# draft2.net
KiCad netlist of a schematic drawn in EAGLE
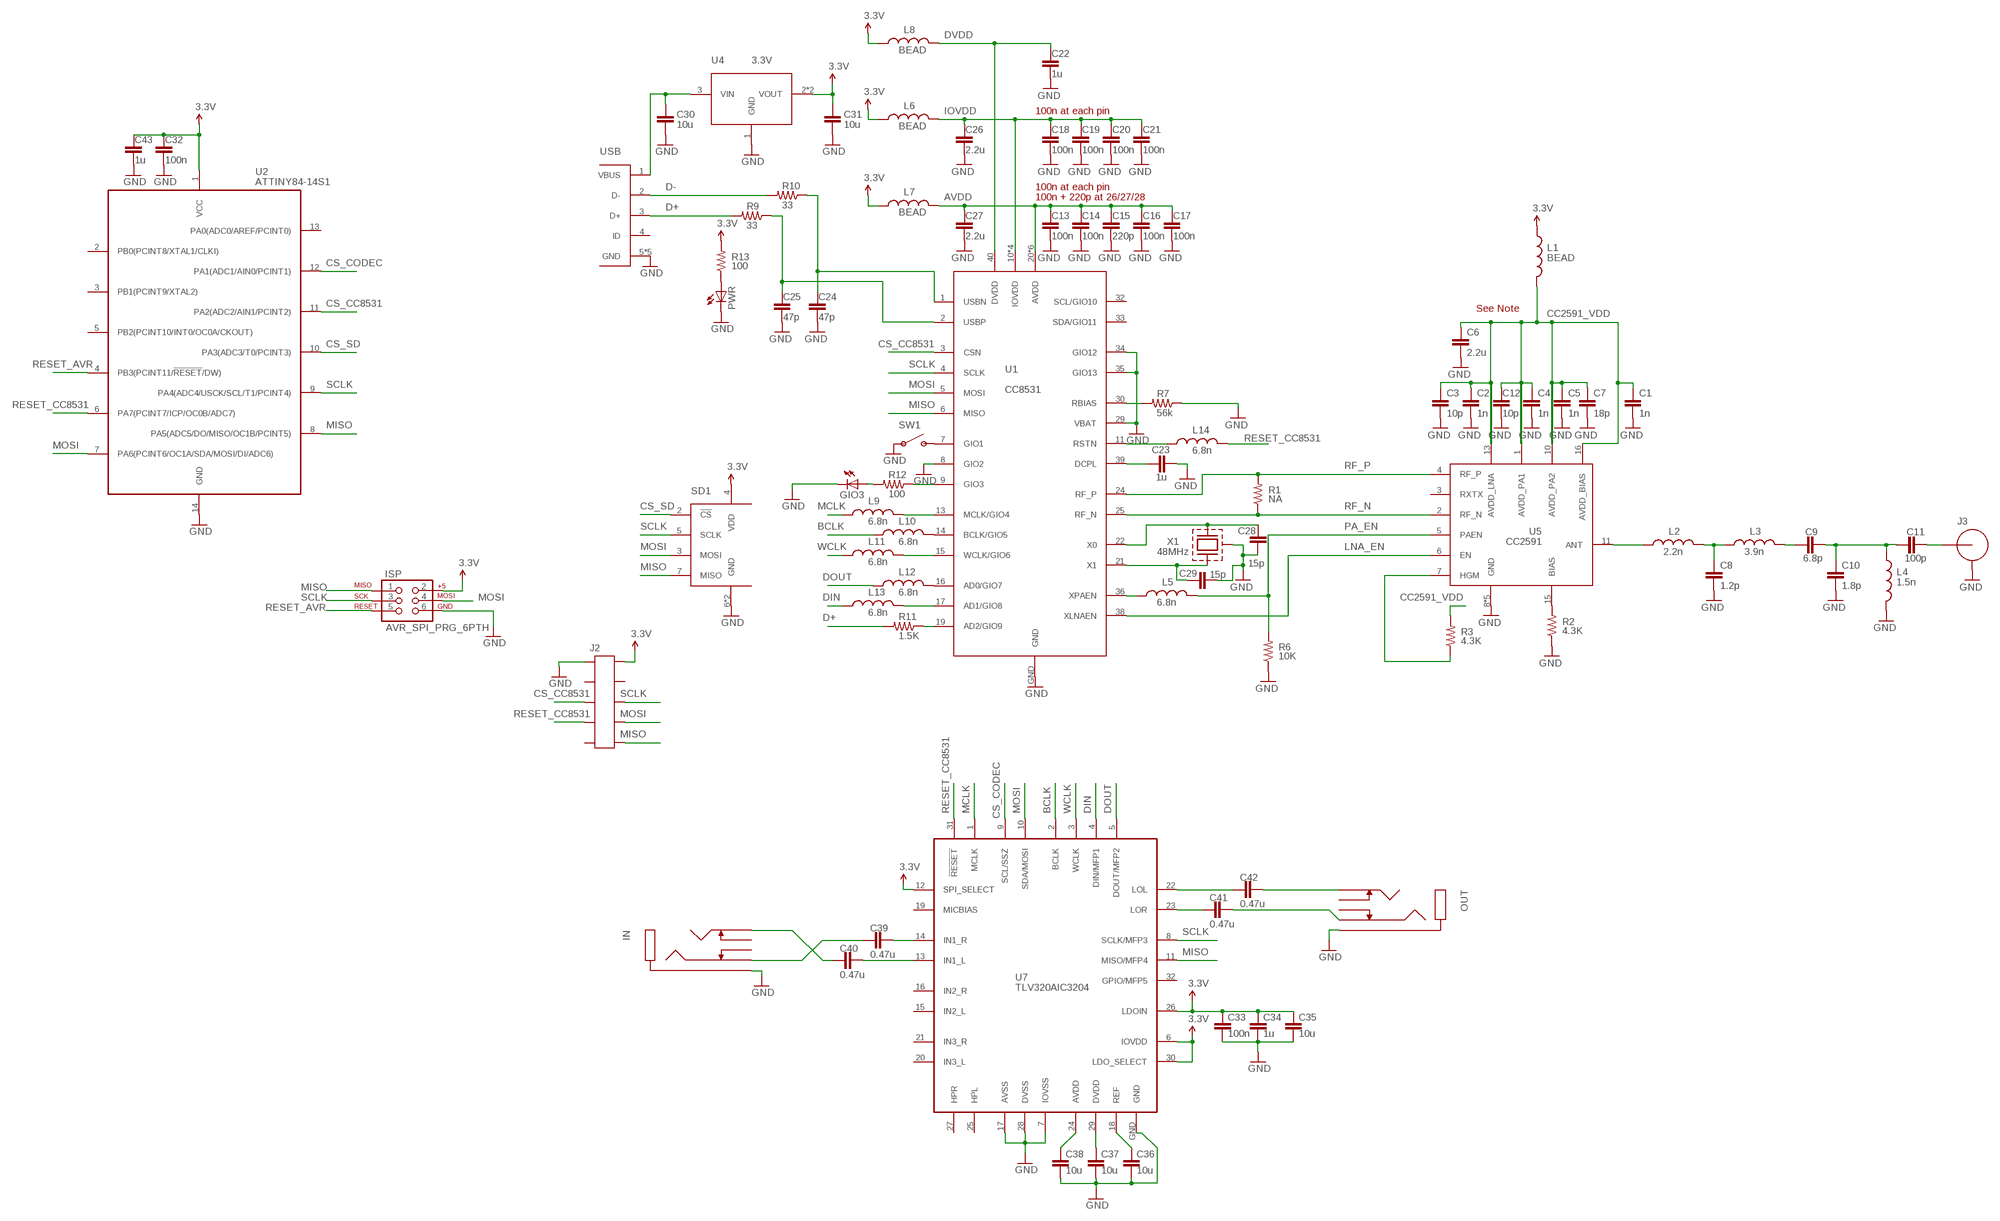
[diagram p0: schematic, sheet 1]

(export (version "E")
  (design (tool "Eeschema 10.0.6"))
  (components
    (comp (ref "C1")
      (value "1n")
      (footprint "eagle-import:C0603")
      (libsource (lib "eagle-import") (part "C-EUC0603"))
    )
    (comp (ref "C2")
      (value "1n")
      (footprint "eagle-import:C0603")
      (libsource (lib "eagle-import") (part "C-EUC0603"))
    )
    (comp (ref "C3")
      (value "10p")
      (footprint "eagle-import:C0603")
      (libsource (lib "eagle-import") (part "C-EUC0603"))
    )
    (comp (ref "C4")
      (value "1n")
      (footprint "eagle-import:C0603")
      (libsource (lib "eagle-import") (part "C-EUC0603"))
    )
    (comp (ref "C5")
      (value "1n")
      (footprint "eagle-import:C0603")
      (libsource (lib "eagle-import") (part "C-EUC0603"))
    )
    (comp (ref "C6")
      (value "2.2u")
      (footprint "eagle-import:C0603")
      (libsource (lib "eagle-import") (part "C-EUC0603"))
    )
    (comp (ref "C7")
      (value "18p")
      (footprint "eagle-import:C0603")
      (libsource (lib "eagle-import") (part "C-EUC0603"))
    )
    (comp (ref "C8")
      (value "1.2p")
      (footprint "eagle-import:C0603")
      (libsource (lib "eagle-import") (part "C-EUC0603"))
    )
    (comp (ref "C9")
      (value "6.8p")
      (footprint "eagle-import:C0603")
      (libsource (lib "eagle-import") (part "C-EUC0603"))
    )
    (comp (ref "C10")
      (value "1.8p")
      (footprint "eagle-import:C0603")
      (libsource (lib "eagle-import") (part "C-EUC0603"))
    )
    (comp (ref "C11")
      (value "100p")
      (footprint "eagle-import:C0603")
      (libsource (lib "eagle-import") (part "C-EUC0603"))
    )
    (comp (ref "C12")
      (value "10p")
      (footprint "eagle-import:C0603")
      (libsource (lib "eagle-import") (part "C-EUC0603"))
    )
    (comp (ref "C13")
      (value "100n")
      (footprint "eagle-import:C0603")
      (libsource (lib "eagle-import") (part "C-EUC0603"))
    )
    (comp (ref "C14")
      (value "100n")
      (footprint "eagle-import:C0603")
      (libsource (lib "eagle-import") (part "C-EUC0603"))
    )
    (comp (ref "C15")
      (value "220p")
      (footprint "eagle-import:C0603")
      (libsource (lib "eagle-import") (part "C-EUC0603"))
    )
    (comp (ref "C16")
      (value "100n")
      (footprint "eagle-import:C0603")
      (libsource (lib "eagle-import") (part "C-EUC0603"))
    )
    (comp (ref "C17")
      (value "100n")
      (footprint "eagle-import:C0603")
      (libsource (lib "eagle-import") (part "C-EUC0603"))
    )
    (comp (ref "C18")
      (value "100n")
      (footprint "eagle-import:C0603")
      (libsource (lib "eagle-import") (part "C-EUC0603"))
    )
    (comp (ref "C19")
      (value "100n")
      (footprint "eagle-import:C0603")
      (libsource (lib "eagle-import") (part "C-EUC0603"))
    )
    (comp (ref "C20")
      (value "100n")
      (footprint "eagle-import:C0603")
      (libsource (lib "eagle-import") (part "C-EUC0603"))
    )
    (comp (ref "C21")
      (value "100n")
      (footprint "eagle-import:C0603")
      (libsource (lib "eagle-import") (part "C-EUC0603"))
    )
    (comp (ref "C22")
      (value "1u")
      (footprint "eagle-import:C0603")
      (libsource (lib "eagle-import") (part "C-EUC0603"))
    )
    (comp (ref "C23")
      (value "1u")
      (footprint "eagle-import:C0603")
      (libsource (lib "eagle-import") (part "C-EUC0603"))
    )
    (comp (ref "C24")
      (value "47p")
      (footprint "eagle-import:C0603")
      (libsource (lib "eagle-import") (part "C-EUC0603"))
    )
    (comp (ref "C25")
      (value "47p")
      (footprint "eagle-import:C0603")
      (libsource (lib "eagle-import") (part "C-EUC0603"))
    )
    (comp (ref "C26")
      (value "2.2u")
      (footprint "eagle-import:C0603")
      (libsource (lib "eagle-import") (part "C-EUC0603"))
    )
    (comp (ref "C27")
      (value "2.2u")
      (footprint "eagle-import:C0603")
      (libsource (lib "eagle-import") (part "C-EUC0603"))
    )
    (comp (ref "C28")
      (value "15p")
      (footprint "eagle-import:C0603")
      (libsource (lib "eagle-import") (part "C-EUC0603"))
    )
    (comp (ref "C29")
      (value "15p")
      (footprint "eagle-import:C0603")
      (libsource (lib "eagle-import") (part "C-EUC0603"))
    )
    (comp (ref "C30")
      (value "10u")
      (footprint "eagle-import:C0603")
      (libsource (lib "eagle-import") (part "C-EUC0603"))
    )
    (comp (ref "C31")
      (value "10u")
      (footprint "eagle-import:C0603")
      (libsource (lib "eagle-import") (part "C-EUC0603"))
    )
    (comp (ref "C32")
      (value "100n")
      (footprint "eagle-import:C0603")
      (libsource (lib "eagle-import") (part "C-EUC0603"))
    )
    (comp (ref "C33")
      (value "100n")
      (footprint "eagle-import:C0603")
      (libsource (lib "eagle-import") (part "C-EUC0603"))
    )
    (comp (ref "C34")
      (value "1u")
      (footprint "eagle-import:C0603")
      (libsource (lib "eagle-import") (part "C-EUC0603"))
    )
    (comp (ref "C35")
      (value "10u")
      (footprint "eagle-import:C0603")
      (libsource (lib "eagle-import") (part "C-EUC0603"))
    )
    (comp (ref "C36")
      (value "10u")
      (footprint "eagle-import:C0603")
      (libsource (lib "eagle-import") (part "C-EUC0603"))
    )
    (comp (ref "C37")
      (value "10u")
      (footprint "eagle-import:C0603")
      (libsource (lib "eagle-import") (part "C-EUC0603"))
    )
    (comp (ref "C38")
      (value "10u")
      (footprint "eagle-import:C0603")
      (libsource (lib "eagle-import") (part "C-EUC0603"))
    )
    (comp (ref "C39")
      (value "0.47u")
      (footprint "eagle-import:C0603")
      (libsource (lib "eagle-import") (part "C-EUC0603"))
    )
    (comp (ref "C40")
      (value "0.47u")
      (footprint "eagle-import:C0603")
      (libsource (lib "eagle-import") (part "C-EUC0603"))
    )
    (comp (ref "C41")
      (value "0.47u")
      (footprint "eagle-import:C0603")
      (libsource (lib "eagle-import") (part "C-EUC0603"))
    )
    (comp (ref "C42")
      (value "0.47u")
      (footprint "eagle-import:C0603")
      (libsource (lib "eagle-import") (part "C-EUC0603"))
    )
    (comp (ref "C43")
      (value "1u")
      (footprint "eagle-import:C0603")
      (libsource (lib "eagle-import") (part "C-EUC0603"))
    )
    (comp (ref "GIO3")
      (value "LEDCHIP-LED0603")
      (footprint "eagle-import:CHIP-LED0603")
      (libsource (lib "eagle-import") (part "LEDCHIP-LED0603"))
    )
    (comp (ref "IN")
      (value "PHONE_SW")
      (footprint "eagle-import:35RAPC4BV4")
      (libsource (lib "eagle-import") (part "PHONE_SW"))
    )
    (comp (ref "ISP")
      (value "AVR_SPI_PRG_6PTH")
      (footprint "eagle-import:2X3")
      (libsource (lib "eagle-import") (part "AVR_SPI_PRG_6PTH"))
    )
    (comp (ref "J2")
      (value "HEADER-10P-SMD-MALE")
      (footprint "eagle-import:10P-0.05-HEADER")
      (libsource (lib "eagle-import") (part "HEADER-10P-SMD-MALE"))
    )
    (comp (ref "J3")
      (value "SMA")
      (footprint "eagle-import:CONSMA003.031")
      (libsource (lib "eagle-import") (part "SMA"))
    )
    (comp (ref "L1")
      (value "BEAD")
      (footprint "eagle-import:0603")
      (libsource (lib "eagle-import") (part "INDUCTOR0603"))
    )
    (comp (ref "L2")
      (value "2.2n")
      (footprint "eagle-import:0603")
      (libsource (lib "eagle-import") (part "INDUCTOR0603"))
    )
    (comp (ref "L3")
      (value "3.9n")
      (footprint "eagle-import:0603")
      (libsource (lib "eagle-import") (part "INDUCTOR0603"))
    )
    (comp (ref "L4")
      (value "1.5n")
      (footprint "eagle-import:0603")
      (libsource (lib "eagle-import") (part "INDUCTOR0603"))
    )
    (comp (ref "L5")
      (value "6.8n")
      (footprint "eagle-import:0603")
      (libsource (lib "eagle-import") (part "INDUCTOR0603"))
    )
    (comp (ref "L6")
      (value "BEAD")
      (footprint "eagle-import:0603")
      (libsource (lib "eagle-import") (part "INDUCTOR0603"))
    )
    (comp (ref "L7")
      (value "BEAD")
      (footprint "eagle-import:0603")
      (libsource (lib "eagle-import") (part "INDUCTOR0603"))
    )
    (comp (ref "L8")
      (value "BEAD")
      (footprint "eagle-import:0603")
      (libsource (lib "eagle-import") (part "INDUCTOR0603"))
    )
    (comp (ref "L9")
      (value "6.8n")
      (footprint "eagle-import:0603")
      (libsource (lib "eagle-import") (part "INDUCTOR0603"))
    )
    (comp (ref "L10")
      (value "6.8n")
      (footprint "eagle-import:0603")
      (libsource (lib "eagle-import") (part "INDUCTOR0603"))
    )
    (comp (ref "L11")
      (value "6.8n")
      (footprint "eagle-import:0603")
      (libsource (lib "eagle-import") (part "INDUCTOR0603"))
    )
    (comp (ref "L12")
      (value "6.8n")
      (footprint "eagle-import:0603")
      (libsource (lib "eagle-import") (part "INDUCTOR0603"))
    )
    (comp (ref "L13")
      (value "6.8n")
      (footprint "eagle-import:0603")
      (libsource (lib "eagle-import") (part "INDUCTOR0603"))
    )
    (comp (ref "L14")
      (value "6.8n")
      (footprint "eagle-import:0603")
      (libsource (lib "eagle-import") (part "INDUCTOR0603"))
    )
    (comp (ref "OUT")
      (value "PHONE_SW")
      (footprint "eagle-import:35RAPC4BV4")
      (libsource (lib "eagle-import") (part "PHONE_SW"))
    )
    (comp (ref "PWR")
      (value "LEDCHIP-LED0603")
      (footprint "eagle-import:CHIP-LED0603")
      (libsource (lib "eagle-import") (part "LEDCHIP-LED0603"))
    )
    (comp (ref "R1")
      (value "NA")
      (footprint "eagle-import:R0603")
      (libsource (lib "eagle-import") (part "R-US_R0603"))
    )
    (comp (ref "R2")
      (value "4.3K")
      (footprint "eagle-import:R0603")
      (libsource (lib "eagle-import") (part "R-US_R0603"))
    )
    (comp (ref "R3")
      (value "4.3K")
      (footprint "eagle-import:R0603")
      (libsource (lib "eagle-import") (part "R-US_R0603"))
    )
    (comp (ref "R6")
      (value "10K")
      (footprint "eagle-import:R0603")
      (libsource (lib "eagle-import") (part "R-US_R0603"))
    )
    (comp (ref "R7")
      (value "56k")
      (footprint "eagle-import:R0603")
      (libsource (lib "eagle-import") (part "R-US_R0603"))
    )
    (comp (ref "R9")
      (value "33")
      (footprint "eagle-import:R0603")
      (libsource (lib "eagle-import") (part "R-US_R0603"))
    )
    (comp (ref "R10")
      (value "33")
      (footprint "eagle-import:R0603")
      (libsource (lib "eagle-import") (part "R-US_R0603"))
    )
    (comp (ref "R11")
      (value "1.5K")
      (footprint "eagle-import:R0603")
      (libsource (lib "eagle-import") (part "R-US_R0603"))
    )
    (comp (ref "R12")
      (value "100")
      (footprint "eagle-import:R0603")
      (libsource (lib "eagle-import") (part "R-US_R0603"))
    )
    (comp (ref "R13")
      (value "100")
      (footprint "eagle-import:R0603")
      (libsource (lib "eagle-import") (part "R-US_R0603"))
    )
    (comp (ref "SD1")
      (value "MICROSDDM3AT")
      (footprint "eagle-import:DM3AT")
      (libsource (lib "eagle-import") (part "MICROSDDM3AT"))
    )
    (comp (ref "SW1")
      (value "SPST-SMD")
      (footprint "eagle-import:TACT_SW")
      (libsource (lib "eagle-import") (part "SPST-SMD"))
    )
    (comp (ref "U1")
      (value "CC8531")
      (footprint "eagle-import:S-PVQFN-N40")
      (libsource (lib "eagle-import") (part "CC8531"))
    )
    (comp (ref "U2")
      (value "ATTINY84-14S1")
      (footprint "eagle-import:SOIC14")
      (libsource (lib "eagle-import") (part "ATTINY84-14S1"))
    )
    (comp (ref "U4")
      (value "3.3V")
      (footprint "eagle-import:SOT-223")
      (libsource (lib "eagle-import") (part "NX1117C"))
    )
    (comp (ref "U5")
      (value "CC2591")
      (footprint "eagle-import:S-PVQFN-N16")
      (libsource (lib "eagle-import") (part "CC2591"))
    )
    (comp (ref "U7")
      (value "TLV320AIC3204")
      (footprint "eagle-import:S-PVQFN-N32")
      (libsource (lib "eagle-import") (part "TLV320AIC3204"))
    )
    (comp (ref "USB")
      (value "USB_MICRO_AB")
      (footprint "eagle-import:USB_MICRO_AB")
      (libsource (lib "eagle-import") (part "USB_MICRO_AB"))
    )
    (comp (ref "X1")
      (value "48MHz")
      (footprint "eagle-import:ABM3C")
      (libsource (lib "eagle-import") (part "XTAL-ABRACONABM3C"))
    )
  )
  (nets
    (net (code "1") (name "/AVDD") (class "Default")
      (node (ref "C13") (pin "1") (pinfunction "1_1") (pintype "passive"))
      (node (ref "C14") (pin "1") (pinfunction "1_1") (pintype "passive"))
      (node (ref "C15") (pin "1") (pinfunction "1_1") (pintype "passive"))
      (node (ref "C16") (pin "1") (pinfunction "1_1") (pintype "passive"))
      (node (ref "C17") (pin "1") (pinfunction "1_1") (pintype "passive"))
      (node (ref "C27") (pin "1") (pinfunction "1_1") (pintype "passive"))
      (node (ref "L7") (pin "2") (pinfunction "2_2") (pintype "passive"))
      (node (ref "U1") (pin "20") (pinfunction "AVDD_20") (pintype "bidirectional"))
      (node (ref "U1") (pin "23") (pinfunction "AVDD_23") (pintype "bidirectional"))
      (node (ref "U1") (pin "26") (pinfunction "AVDD_26") (pintype "bidirectional"))
      (node (ref "U1") (pin "27") (pinfunction "AVDD_27") (pintype "bidirectional"))
      (node (ref "U1") (pin "28") (pinfunction "AVDD_28") (pintype "bidirectional"))
      (node (ref "U1") (pin "31") (pinfunction "AVDD_31") (pintype "bidirectional"))
    )
    (net (code "2") (name "/BCLK") (class "Default")
      (node (ref "L10") (pin "1") (pinfunction "1_1") (pintype "passive"))
      (node (ref "U7") (pin "2") (pinfunction "BCLK_2") (pintype "bidirectional"))
    )
    (net (code "3") (name "/CC2591_VDD") (class "Default")
      (node (ref "C1") (pin "1") (pinfunction "1_1") (pintype "passive"))
      (node (ref "C12") (pin "1") (pinfunction "1_1") (pintype "passive"))
      (node (ref "C2") (pin "1") (pinfunction "1_1") (pintype "passive"))
      (node (ref "C3") (pin "1") (pinfunction "1_1") (pintype "passive"))
      (node (ref "C4") (pin "1") (pinfunction "1_1") (pintype "passive"))
      (node (ref "C5") (pin "1") (pinfunction "1_1") (pintype "passive"))
      (node (ref "C6") (pin "1") (pinfunction "1_1") (pintype "passive"))
      (node (ref "C7") (pin "1") (pinfunction "1_1") (pintype "passive"))
      (node (ref "L1") (pin "2") (pinfunction "2_2") (pintype "passive"))
      (node (ref "R3") (pin "2") (pinfunction "2_2") (pintype "passive"))
      (node (ref "U5") (pin "1") (pinfunction "AVDD_PA1_1") (pintype "bidirectional"))
      (node (ref "U5") (pin "10") (pinfunction "AVDD_PA2_10") (pintype "bidirectional"))
      (node (ref "U5") (pin "13") (pinfunction "AVDD_LNA_13") (pintype "bidirectional"))
      (node (ref "U5") (pin "16") (pinfunction "AVDD_BIAS_16") (pintype "bidirectional"))
    )
    (net (code "4") (name "/CS_CC8531") (class "Default")
      (node (ref "J2") (pin "5") (pinfunction "5_5") (pintype "bidirectional"))
      (node (ref "U1") (pin "3") (pinfunction "CSN_3") (pintype "bidirectional"))
      (node (ref "U2") (pin "11") (pinfunction "PA2(ADC2/AIN1/PCINT2)_11") (pintype "bidirectional"))
    )
    (net (code "5") (name "/CS_CODEC") (class "Default")
      (node (ref "U2") (pin "12") (pinfunction "PA1(ADC1/AIN0/PCINT1)_12") (pintype "bidirectional"))
      (node (ref "U7") (pin "9") (pinfunction "SCL/SSZ_9") (pintype "bidirectional"))
    )
    (net (code "6") (name "/CS_SD") (class "Default")
      (node (ref "SD1") (pin "2") (pinfunction "~{CS}_2") (pintype "bidirectional"))
      (node (ref "U2") (pin "10") (pinfunction "PA3(ADC3/T0/PCINT3)_10") (pintype "bidirectional"))
    )
    (net (code "7") (name "/D+") (class "Default")
      (node (ref "R11") (pin "2") (pinfunction "2_2") (pintype "passive"))
      (node (ref "R9") (pin "2") (pinfunction "2_2") (pintype "passive"))
      (node (ref "USB") (pin "3") (pinfunction "D+_3") (pintype "bidirectional"))
    )
    (net (code "8") (name "/D-") (class "Default")
      (node (ref "R10") (pin "2") (pinfunction "2_2") (pintype "passive"))
      (node (ref "USB") (pin "2") (pinfunction "D-_2") (pintype "bidirectional"))
    )
    (net (code "9") (name "/DIN") (class "Default")
      (node (ref "L13") (pin "1") (pinfunction "1_1") (pintype "passive"))
      (node (ref "U7") (pin "4") (pinfunction "DIN/MFP1_4") (pintype "bidirectional"))
    )
    (net (code "10") (name "/DOUT") (class "Default")
      (node (ref "L12") (pin "1") (pinfunction "1_1") (pintype "passive"))
      (node (ref "U7") (pin "5") (pinfunction "DOUT/MFP2_5") (pintype "bidirectional"))
    )
    (net (code "11") (name "/DVDD") (class "Default")
      (node (ref "C22") (pin "1") (pinfunction "1_1") (pintype "passive"))
      (node (ref "L8") (pin "2") (pinfunction "2_2") (pintype "passive"))
      (node (ref "U1") (pin "40") (pinfunction "DVDD_40") (pintype "bidirectional"))
    )
    (net (code "12") (name "/IOVDD") (class "Default")
      (node (ref "C18") (pin "1") (pinfunction "1_1") (pintype "passive"))
      (node (ref "C19") (pin "1") (pinfunction "1_1") (pintype "passive"))
      (node (ref "C20") (pin "1") (pinfunction "1_1") (pintype "passive"))
      (node (ref "C21") (pin "1") (pinfunction "1_1") (pintype "passive"))
      (node (ref "C26") (pin "1") (pinfunction "1_1") (pintype "passive"))
      (node (ref "L6") (pin "2") (pinfunction "2_2") (pintype "passive"))
      (node (ref "U1") (pin "10") (pinfunction "IOVDD_10") (pintype "bidirectional"))
      (node (ref "U1") (pin "12") (pinfunction "IOVDD_12") (pintype "bidirectional"))
      (node (ref "U1") (pin "18") (pinfunction "IOVDD_18") (pintype "bidirectional"))
      (node (ref "U1") (pin "37") (pinfunction "IOVDD_37") (pintype "bidirectional"))
    )
    (net (code "13") (name "/LNA_EN") (class "Default")
      (node (ref "U1") (pin "38") (pinfunction "XLNAEN_38") (pintype "bidirectional"))
      (node (ref "U5") (pin "6") (pinfunction "EN_6") (pintype "bidirectional"))
    )
    (net (code "14") (name "/MCLK") (class "Default")
      (node (ref "L9") (pin "1") (pinfunction "1_1") (pintype "passive"))
      (node (ref "U7") (pin "1") (pinfunction "MCLK_1") (pintype "bidirectional"))
    )
    (net (code "15") (name "/MISO") (class "Default")
      (node (ref "ISP") (pin "1") (pinfunction "1_1") (pintype "passive"))
      (node (ref "J2") (pin "10") (pinfunction "10_10") (pintype "bidirectional"))
      (node (ref "SD1") (pin "7") (pinfunction "MISO_7") (pintype "bidirectional"))
      (node (ref "U1") (pin "6") (pinfunction "MISO_6") (pintype "bidirectional"))
      (node (ref "U2") (pin "8") (pinfunction "PA5(ADC5/DO/MISO/OC1B/PCINT5)_8") (pintype "bidirectional"))
      (node (ref "U7") (pin "11") (pinfunction "MISO/MFP4_11") (pintype "bidirectional"))
    )
    (net (code "16") (name "/MOSI") (class "Default")
      (node (ref "ISP") (pin "4") (pinfunction "4_4") (pintype "passive"))
      (node (ref "J2") (pin "8") (pinfunction "8_8") (pintype "bidirectional"))
      (node (ref "SD1") (pin "3") (pinfunction "MOSI_3") (pintype "bidirectional"))
      (node (ref "U1") (pin "5") (pinfunction "MOSI_5") (pintype "bidirectional"))
      (node (ref "U2") (pin "7") (pinfunction "PA6(PCINT6/OC1A/SDA/MOSI/DI/ADC6)_7") (pintype "bidirectional"))
      (node (ref "U7") (pin "10") (pinfunction "SDA/MOSI_10") (pintype "bidirectional"))
    )
    (net (code "17") (name "/PA_EN") (class "Default")
      (node (ref "L5") (pin "2") (pinfunction "2_2") (pintype "passive"))
      (node (ref "R6") (pin "2") (pinfunction "2_2") (pintype "passive"))
      (node (ref "U5") (pin "5") (pinfunction "PAEN_5") (pintype "bidirectional"))
    )
    (net (code "18") (name "/RESET_AVR") (class "Default")
      (node (ref "ISP") (pin "5") (pinfunction "5_5") (pintype "passive"))
      (node (ref "U2") (pin "4") (pinfunction "PB3(PCINT11/~{RESET}/DW)_4") (pintype "bidirectional"))
    )
    (net (code "19") (name "/RESET_CC8531") (class "Default")
      (node (ref "J2") (pin "7") (pinfunction "7_7") (pintype "bidirectional"))
      (node (ref "L14") (pin "2") (pinfunction "2_2") (pintype "passive"))
      (node (ref "U2") (pin "6") (pinfunction "PA7(PCINT7/ICP/OC0B/ADC7)_6") (pintype "bidirectional"))
      (node (ref "U7") (pin "31") (pinfunction "~{RESET}_31") (pintype "bidirectional"))
    )
    (net (code "20") (name "/RF_N") (class "Default")
      (node (ref "R1") (pin "1") (pinfunction "1_1") (pintype "passive"))
      (node (ref "U1") (pin "25") (pinfunction "RF_N_25") (pintype "bidirectional"))
      (node (ref "U5") (pin "2") (pinfunction "RF_N_2") (pintype "bidirectional"))
    )
    (net (code "21") (name "/RF_P") (class "Default")
      (node (ref "R1") (pin "2") (pinfunction "2_2") (pintype "passive"))
      (node (ref "U1") (pin "24") (pinfunction "RF_P_24") (pintype "bidirectional"))
      (node (ref "U5") (pin "4") (pinfunction "RF_P_4") (pintype "bidirectional"))
    )
    (net (code "22") (name "/SCLK") (class "Default")
      (node (ref "ISP") (pin "3") (pinfunction "3_3") (pintype "passive"))
      (node (ref "J2") (pin "6") (pinfunction "6_6") (pintype "bidirectional"))
      (node (ref "SD1") (pin "5") (pinfunction "SCLK_5") (pintype "bidirectional"))
      (node (ref "U1") (pin "4") (pinfunction "SCLK_4") (pintype "bidirectional"))
      (node (ref "U2") (pin "9") (pinfunction "PA4(ADC4/USCK/SCL/T1/PCINT4)_9") (pintype "bidirectional"))
      (node (ref "U7") (pin "8") (pinfunction "SCLK/MFP3_8") (pintype "bidirectional"))
    )
    (net (code "23") (name "/WCLK") (class "Default")
      (node (ref "L11") (pin "1") (pinfunction "1_1") (pintype "passive"))
      (node (ref "U7") (pin "3") (pinfunction "WCLK_3") (pintype "bidirectional"))
    )
    (net (code "24") (name "3.3V") (class "Default")
      (node (ref "C31") (pin "1") (pinfunction "1_1") (pintype "passive"))
      (node (ref "C32") (pin "1") (pinfunction "1_1") (pintype "passive"))
      (node (ref "C33") (pin "1") (pinfunction "1_1") (pintype "passive"))
      (node (ref "C34") (pin "1") (pinfunction "1_1") (pintype "passive"))
      (node (ref "C35") (pin "1") (pinfunction "1_1") (pintype "passive"))
      (node (ref "C43") (pin "1") (pinfunction "1_1") (pintype "passive"))
      (node (ref "ISP") (pin "2") (pinfunction "2_2") (pintype "passive"))
      (node (ref "J2") (pin "2") (pinfunction "2_2") (pintype "bidirectional"))
      (node (ref "L1") (pin "1") (pinfunction "1_1") (pintype "passive"))
      (node (ref "L6") (pin "1") (pinfunction "1_1") (pintype "passive"))
      (node (ref "L7") (pin "1") (pinfunction "1_1") (pintype "passive"))
      (node (ref "L8") (pin "1") (pinfunction "1_1") (pintype "passive"))
      (node (ref "R13") (pin "2") (pinfunction "2_2") (pintype "passive"))
      (node (ref "SD1") (pin "4") (pinfunction "VDD_4") (pintype "bidirectional"))
      (node (ref "U2") (pin "1") (pinfunction "VCC_1") (pintype "bidirectional"))
      (node (ref "U4") (pin "2") (pinfunction "VOUT_2") (pintype "bidirectional"))
      (node (ref "U4") (pin "4") (pinfunction "VOUT_4") (pintype "bidirectional"))
      (node (ref "U7") (pin "12") (pinfunction "SPI_SELECT_12") (pintype "bidirectional"))
      (node (ref "U7") (pin "26") (pinfunction "LDOIN_26") (pintype "bidirectional"))
      (node (ref "U7") (pin "30") (pinfunction "LDO_SELECT_30") (pintype "bidirectional"))
      (node (ref "U7") (pin "6") (pinfunction "IOVDD_6") (pintype "bidirectional"))
    )
    (net (code "25") (name "GND") (class "Default")
      (node (ref "C1") (pin "2") (pinfunction "2_2") (pintype "passive"))
      (node (ref "C10") (pin "2") (pinfunction "2_2") (pintype "passive"))
      (node (ref "C12") (pin "2") (pinfunction "2_2") (pintype "passive"))
      (node (ref "C13") (pin "2") (pinfunction "2_2") (pintype "passive"))
      (node (ref "C14") (pin "2") (pinfunction "2_2") (pintype "passive"))
      (node (ref "C15") (pin "2") (pinfunction "2_2") (pintype "passive"))
      (node (ref "C16") (pin "2") (pinfunction "2_2") (pintype "passive"))
      (node (ref "C17") (pin "2") (pinfunction "2_2") (pintype "passive"))
      (node (ref "C18") (pin "2") (pinfunction "2_2") (pintype "passive"))
      (node (ref "C19") (pin "2") (pinfunction "2_2") (pintype "passive"))
      (node (ref "C2") (pin "2") (pinfunction "2_2") (pintype "passive"))
      (node (ref "C20") (pin "2") (pinfunction "2_2") (pintype "passive"))
      (node (ref "C21") (pin "2") (pinfunction "2_2") (pintype "passive"))
      (node (ref "C22") (pin "2") (pinfunction "2_2") (pintype "passive"))
      (node (ref "C23") (pin "2") (pinfunction "2_2") (pintype "passive"))
      (node (ref "C24") (pin "2") (pinfunction "2_2") (pintype "passive"))
      (node (ref "C25") (pin "2") (pinfunction "2_2") (pintype "passive"))
      (node (ref "C26") (pin "2") (pinfunction "2_2") (pintype "passive"))
      (node (ref "C27") (pin "2") (pinfunction "2_2") (pintype "passive"))
      (node (ref "C28") (pin "2") (pinfunction "2_2") (pintype "passive"))
      (node (ref "C29") (pin "2") (pinfunction "2_2") (pintype "passive"))
      (node (ref "C3") (pin "2") (pinfunction "2_2") (pintype "passive"))
      (node (ref "C30") (pin "2") (pinfunction "2_2") (pintype "passive"))
      (node (ref "C31") (pin "2") (pinfunction "2_2") (pintype "passive"))
      (node (ref "C32") (pin "2") (pinfunction "2_2") (pintype "passive"))
      (node (ref "C33") (pin "2") (pinfunction "2_2") (pintype "passive"))
      (node (ref "C34") (pin "2") (pinfunction "2_2") (pintype "passive"))
      (node (ref "C35") (pin "2") (pinfunction "2_2") (pintype "passive"))
      (node (ref "C36") (pin "2") (pinfunction "2_2") (pintype "passive"))
      (node (ref "C37") (pin "2") (pinfunction "2_2") (pintype "passive"))
      (node (ref "C38") (pin "2") (pinfunction "2_2") (pintype "passive"))
      (node (ref "C4") (pin "2") (pinfunction "2_2") (pintype "passive"))
      (node (ref "C43") (pin "2") (pinfunction "2_2") (pintype "passive"))
      (node (ref "C5") (pin "2") (pinfunction "2_2") (pintype "passive"))
      (node (ref "C6") (pin "2") (pinfunction "2_2") (pintype "passive"))
      (node (ref "C7") (pin "2") (pinfunction "2_2") (pintype "passive"))
      (node (ref "C8") (pin "2") (pinfunction "2_2") (pintype "passive"))
      (node (ref "GIO3") (pin "C") (pinfunction "C_C") (pintype "passive"))
      (node (ref "IN") (pin "1") (pinfunction "GND_1") (pintype "bidirectional"))
      (node (ref "ISP") (pin "6") (pinfunction "6_6") (pintype "passive"))
      (node (ref "J2") (pin "1") (pinfunction "1_1") (pintype "bidirectional"))
      (node (ref "J3") (pin "GND1") (pinfunction "GND_GND1") (pintype "bidirectional"))
      (node (ref "J3") (pin "GND2") (pinfunction "GND_GND2") (pintype "bidirectional"))
      (node (ref "J3") (pin "GND3") (pinfunction "GND_GND3") (pintype "bidirectional"))
      (node (ref "J3") (pin "GND4") (pinfunction "GND_GND4") (pintype "bidirectional"))
      (node (ref "L4") (pin "2") (pinfunction "2_2") (pintype "passive"))
      (node (ref "OUT") (pin "1") (pinfunction "GND_1") (pintype "bidirectional"))
      (node (ref "PWR") (pin "C") (pinfunction "C_C") (pintype "passive"))
      (node (ref "R2") (pin "1") (pinfunction "1_1") (pintype "passive"))
      (node (ref "R6") (pin "1") (pinfunction "1_1") (pintype "passive"))
      (node (ref "R7") (pin "1") (pinfunction "1_1") (pintype "passive"))
      (node (ref "SD1") (pin "6") (pinfunction "GND_6") (pintype "bidirectional"))
      (node (ref "SD1") (pin "GND") (pinfunction "GND_GND") (pintype "bidirectional"))
      (node (ref "SW1") (pin "1") (pinfunction "P$1_1") (pintype "bidirectional"))
      (node (ref "SW1") (pin "2") (pinfunction "P$1_2") (pintype "bidirectional"))
      (node (ref "U1") (pin "29") (pinfunction "VBAT_29") (pintype "bidirectional"))
      (node (ref "U1") (pin "34") (pinfunction "GIO12_34") (pintype "bidirectional"))
      (node (ref "U1") (pin "35") (pinfunction "GIO13_35") (pintype "bidirectional"))
      (node (ref "U1") (pin "8") (pinfunction "GIO2_8") (pintype "bidirectional"))
      (node (ref "U1") (pin "GND") (pinfunction "GND_GND") (pintype "bidirectional"))
      (node (ref "U2") (pin "14") (pinfunction "GND_14") (pintype "bidirectional"))
      (node (ref "U4") (pin "1") (pinfunction "GND_1") (pintype "bidirectional"))
      (node (ref "U5") (pin "12") (pinfunction "GND_12") (pintype "bidirectional"))
      (node (ref "U5") (pin "14") (pinfunction "GND_14") (pintype "bidirectional"))
      (node (ref "U5") (pin "8") (pinfunction "GND_8") (pintype "bidirectional"))
      (node (ref "U5") (pin "9") (pinfunction "GND_9") (pintype "bidirectional"))
      (node (ref "U5") (pin "GND") (pinfunction "GND_GND") (pintype "bidirectional"))
      (node (ref "U7") (pin "17") (pinfunction "AVSS_17") (pintype "bidirectional"))
      (node (ref "U7") (pin "28") (pinfunction "DVSS_28") (pintype "bidirectional"))
      (node (ref "U7") (pin "7") (pinfunction "IOVSS_7") (pintype "bidirectional"))
      (node (ref "U7") (pin "GND") (pinfunction "GND_GND") (pintype "bidirectional"))
      (node (ref "USB") (pin "5") (pinfunction "GND_5") (pintype "bidirectional"))
      (node (ref "USB") (pin "GND1") (pinfunction "GND_GND1") (pintype "bidirectional"))
      (node (ref "USB") (pin "GND2") (pinfunction "GND_GND2") (pintype "bidirectional"))
      (node (ref "USB") (pin "GND3") (pinfunction "GND_GND3") (pintype "bidirectional"))
      (node (ref "USB") (pin "GND4") (pinfunction "GND_GND4") (pintype "bidirectional"))
      (node (ref "X1") (pin "2") (pinfunction "CASE_2") (pintype "passive"))
      (node (ref "X1") (pin "4") (pinfunction "CASE_4") (pintype "passive"))
    )
    (net (code "26") (name "Net-(C8-Pad1)") (class "Default")
      (node (ref "C8") (pin "1") (pinfunction "1_1") (pintype "passive"))
      (node (ref "L2") (pin "2") (pinfunction "2_2") (pintype "passive"))
      (node (ref "L3") (pin "1") (pinfunction "1_1") (pintype "passive"))
    )
    (net (code "27") (name "Net-(C9-Pad1)") (class "Default")
      (node (ref "C9") (pin "1") (pinfunction "1_1") (pintype "passive"))
      (node (ref "L3") (pin "2") (pinfunction "2_2") (pintype "passive"))
    )
    (net (code "28") (name "Net-(C10-Pad1)") (class "Default")
      (node (ref "C10") (pin "1") (pinfunction "1_1") (pintype "passive"))
      (node (ref "C11") (pin "1") (pinfunction "1_1") (pintype "passive"))
      (node (ref "C9") (pin "2") (pinfunction "2_2") (pintype "passive"))
      (node (ref "L4") (pin "1") (pinfunction "1_1") (pintype "passive"))
    )
    (net (code "29") (name "Net-(C11-Pad2)") (class "Default")
      (node (ref "C11") (pin "2") (pinfunction "2_2") (pintype "passive"))
      (node (ref "J3") (pin "SIG") (pinfunction "SIG_SIG") (pintype "bidirectional"))
    )
    (net (code "30") (name "Net-(GIO3-PadA)") (class "Default")
      (node (ref "GIO3") (pin "A") (pinfunction "A_A") (pintype "passive"))
      (node (ref "R12") (pin "2") (pinfunction "2_2") (pintype "passive"))
    )
    (net (code "31") (name "Net-(IN-L)") (class "Default")
      (node (ref "C40") (pin "1") (pinfunction "1_1") (pintype "passive"))
      (node (ref "IN") (pin "2") (pinfunction "L_2") (pintype "bidirectional"))
    )
    (net (code "32") (name "Net-(IN-R)") (class "Default")
      (node (ref "C39") (pin "1") (pinfunction "1_1") (pintype "passive"))
      (node (ref "IN") (pin "4") (pinfunction "R_4") (pintype "bidirectional"))
    )
    (net (code "33") (name "Net-(OUT-L)") (class "Default")
      (node (ref "C42") (pin "2") (pinfunction "2_2") (pintype "passive"))
      (node (ref "OUT") (pin "2") (pinfunction "L_2") (pintype "bidirectional"))
    )
    (net (code "34") (name "Net-(OUT-R)") (class "Default")
      (node (ref "C41") (pin "2") (pinfunction "2_2") (pintype "passive"))
      (node (ref "OUT") (pin "4") (pinfunction "R_4") (pintype "bidirectional"))
    )
    (net (code "35") (name "Net-(PWR-PadA)") (class "Default")
      (node (ref "PWR") (pin "A") (pinfunction "A_A") (pintype "passive"))
      (node (ref "R13") (pin "1") (pinfunction "1_1") (pintype "passive"))
    )
    (net (code "36") (name "Net-(U1-AD0{slash}GIO7)") (class "Default")
      (node (ref "L12") (pin "2") (pinfunction "2_2") (pintype "passive"))
      (node (ref "U1") (pin "16") (pinfunction "AD0/GIO7_16") (pintype "bidirectional"))
    )
    (net (code "37") (name "Net-(U1-AD1{slash}GIO8)") (class "Default")
      (node (ref "L13") (pin "2") (pinfunction "2_2") (pintype "passive"))
      (node (ref "U1") (pin "17") (pinfunction "AD1/GIO8_17") (pintype "bidirectional"))
    )
    (net (code "38") (name "Net-(U1-AD2{slash}GIO9)") (class "Default")
      (node (ref "R11") (pin "1") (pinfunction "1_1") (pintype "passive"))
      (node (ref "U1") (pin "19") (pinfunction "AD2/GIO9_19") (pintype "bidirectional"))
    )
    (net (code "39") (name "Net-(U1-BCLK{slash}GIO5)") (class "Default")
      (node (ref "L10") (pin "2") (pinfunction "2_2") (pintype "passive"))
      (node (ref "U1") (pin "14") (pinfunction "BCLK/GIO5_14") (pintype "bidirectional"))
    )
    (net (code "40") (name "Net-(U1-DCPL)") (class "Default")
      (node (ref "C23") (pin "1") (pinfunction "1_1") (pintype "passive"))
      (node (ref "U1") (pin "39") (pinfunction "DCPL_39") (pintype "bidirectional"))
    )
    (net (code "41") (name "Net-(U1-GIO1)") (class "Default")
      (node (ref "SW1") (pin "3") (pinfunction "P$2_3") (pintype "bidirectional"))
      (node (ref "SW1") (pin "4") (pinfunction "P$2_4") (pintype "bidirectional"))
      (node (ref "U1") (pin "7") (pinfunction "GIO1_7") (pintype "bidirectional"))
    )
    (net (code "42") (name "Net-(U1-GIO3)") (class "Default")
      (node (ref "R12") (pin "1") (pinfunction "1_1") (pintype "passive"))
      (node (ref "U1") (pin "9") (pinfunction "GIO3_9") (pintype "bidirectional"))
    )
    (net (code "43") (name "Net-(U1-MCLK{slash}GIO4)") (class "Default")
      (node (ref "L9") (pin "2") (pinfunction "2_2") (pintype "passive"))
      (node (ref "U1") (pin "13") (pinfunction "MCLK/GIO4_13") (pintype "bidirectional"))
    )
    (net (code "44") (name "Net-(U1-RBIAS)") (class "Default")
      (node (ref "R7") (pin "2") (pinfunction "2_2") (pintype "passive"))
      (node (ref "U1") (pin "30") (pinfunction "RBIAS_30") (pintype "bidirectional"))
    )
    (net (code "45") (name "Net-(U1-RSTN)") (class "Default")
      (node (ref "L14") (pin "1") (pinfunction "1_1") (pintype "passive"))
      (node (ref "U1") (pin "11") (pinfunction "RSTN_11") (pintype "bidirectional"))
    )
    (net (code "46") (name "Net-(U1-USBN)") (class "Default")
      (node (ref "C24") (pin "1") (pinfunction "1_1") (pintype "passive"))
      (node (ref "R10") (pin "1") (pinfunction "1_1") (pintype "passive"))
      (node (ref "U1") (pin "1") (pinfunction "USBN_1") (pintype "bidirectional"))
    )
    (net (code "47") (name "Net-(U1-USBP)") (class "Default")
      (node (ref "C25") (pin "1") (pinfunction "1_1") (pintype "passive"))
      (node (ref "R9") (pin "1") (pinfunction "1_1") (pintype "passive"))
      (node (ref "U1") (pin "2") (pinfunction "USBP_2") (pintype "bidirectional"))
    )
    (net (code "48") (name "Net-(U1-WCLK{slash}GIO6)") (class "Default")
      (node (ref "L11") (pin "2") (pinfunction "2_2") (pintype "passive"))
      (node (ref "U1") (pin "15") (pinfunction "WCLK/GIO6_15") (pintype "bidirectional"))
    )
    (net (code "49") (name "Net-(U1-X0)") (class "Default")
      (node (ref "C28") (pin "1") (pinfunction "1_1") (pintype "passive"))
      (node (ref "U1") (pin "22") (pinfunction "X0_22") (pintype "bidirectional"))
      (node (ref "X1") (pin "3") (pinfunction "2_3") (pintype "passive"))
    )
    (net (code "50") (name "Net-(U1-X1)") (class "Default")
      (node (ref "C29") (pin "1") (pinfunction "1_1") (pintype "passive"))
      (node (ref "U1") (pin "21") (pinfunction "X1_21") (pintype "bidirectional"))
      (node (ref "X1") (pin "1") (pinfunction "1_1") (pintype "passive"))
    )
    (net (code "51") (name "Net-(U1-XPAEN)") (class "Default")
      (node (ref "L5") (pin "1") (pinfunction "1_1") (pintype "passive"))
      (node (ref "U1") (pin "36") (pinfunction "XPAEN_36") (pintype "bidirectional"))
    )
    (net (code "52") (name "Net-(U4-VIN)") (class "Default")
      (node (ref "C30") (pin "1") (pinfunction "1_1") (pintype "passive"))
      (node (ref "U4") (pin "3") (pinfunction "VIN_3") (pintype "bidirectional"))
      (node (ref "USB") (pin "1") (pinfunction "VBUS_1") (pintype "bidirectional"))
    )
    (net (code "53") (name "Net-(U5-ANT)") (class "Default")
      (node (ref "L2") (pin "1") (pinfunction "1_1") (pintype "passive"))
      (node (ref "U5") (pin "11") (pinfunction "ANT_11") (pintype "bidirectional"))
    )
    (net (code "54") (name "Net-(U5-BIAS)") (class "Default")
      (node (ref "R2") (pin "2") (pinfunction "2_2") (pintype "passive"))
      (node (ref "U5") (pin "15") (pinfunction "BIAS_15") (pintype "bidirectional"))
    )
    (net (code "55") (name "Net-(U5-HGM)") (class "Default")
      (node (ref "R3") (pin "1") (pinfunction "1_1") (pintype "passive"))
      (node (ref "U5") (pin "7") (pinfunction "HGM_7") (pintype "bidirectional"))
    )
    (net (code "56") (name "Net-(U7-AVDD)") (class "Default")
      (node (ref "C38") (pin "1") (pinfunction "1_1") (pintype "passive"))
      (node (ref "U7") (pin "24") (pinfunction "AVDD_24") (pintype "bidirectional"))
    )
    (net (code "57") (name "Net-(U7-DVDD)") (class "Default")
      (node (ref "C37") (pin "1") (pinfunction "1_1") (pintype "passive"))
      (node (ref "U7") (pin "29") (pinfunction "DVDD_29") (pintype "bidirectional"))
    )
    (net (code "58") (name "Net-(U7-IN1_L)") (class "Default")
      (node (ref "C40") (pin "2") (pinfunction "2_2") (pintype "passive"))
      (node (ref "U7") (pin "13") (pinfunction "IN1_L_13") (pintype "bidirectional"))
    )
    (net (code "59") (name "Net-(U7-IN1_R)") (class "Default")
      (node (ref "C39") (pin "2") (pinfunction "2_2") (pintype "passive"))
      (node (ref "U7") (pin "14") (pinfunction "IN1_R_14") (pintype "bidirectional"))
    )
    (net (code "60") (name "Net-(U7-LOL)") (class "Default")
      (node (ref "C42") (pin "1") (pinfunction "1_1") (pintype "passive"))
      (node (ref "U7") (pin "22") (pinfunction "LOL_22") (pintype "bidirectional"))
    )
    (net (code "61") (name "Net-(U7-LOR)") (class "Default")
      (node (ref "C41") (pin "1") (pinfunction "1_1") (pintype "passive"))
      (node (ref "U7") (pin "23") (pinfunction "LOR_23") (pintype "bidirectional"))
    )
    (net (code "62") (name "Net-(U7-REF)") (class "Default")
      (node (ref "C36") (pin "1") (pinfunction "1_1") (pintype "passive"))
      (node (ref "U7") (pin "18") (pinfunction "REF_18") (pintype "bidirectional"))
    )
    (net (code "63") (name "unconnected-(IN-L_SW-Pad5)") (class "Default")
      (node (ref "IN") (pin "5") (pinfunction "L_SW_5") (pintype "bidirectional"))
    )
    (net (code "64") (name "unconnected-(IN-R_SW-Pad3)") (class "Default")
      (node (ref "IN") (pin "3") (pinfunction "R_SW_3") (pintype "bidirectional"))
    )
    (net (code "65") (name "unconnected-(J2-Pad3)") (class "Default")
      (node (ref "J2") (pin "3") (pinfunction "3_3") (pintype "bidirectional"))
    )
    (net (code "66") (name "unconnected-(J2-Pad4)") (class "Default")
      (node (ref "J2") (pin "4") (pinfunction "4_4") (pintype "bidirectional"))
    )
    (net (code "67") (name "unconnected-(J2-Pad9)") (class "Default")
      (node (ref "J2") (pin "9") (pinfunction "9_9") (pintype "bidirectional"))
    )
    (net (code "68") (name "unconnected-(OUT-L_SW-Pad5)") (class "Default")
      (node (ref "OUT") (pin "5") (pinfunction "L_SW_5") (pintype "bidirectional"))
    )
    (net (code "69") (name "unconnected-(OUT-R_SW-Pad3)") (class "Default")
      (node (ref "OUT") (pin "3") (pinfunction "R_SW_3") (pintype "bidirectional"))
    )
    (net (code "70") (name "unconnected-(U1-SCL{slash}GIO10-Pad32)") (class "Default")
      (node (ref "U1") (pin "32") (pinfunction "SCL/GIO10_32") (pintype "bidirectional"))
    )
    (net (code "71") (name "unconnected-(U1-SDA{slash}GIO11-Pad33)") (class "Default")
      (node (ref "U1") (pin "33") (pinfunction "SDA/GIO11_33") (pintype "bidirectional"))
    )
    (net (code "72") (name "unconnected-(U2-PA0(ADC0{slash}AREF{slash}PCINT0)-Pad13)") (class "Default")
      (node (ref "U2") (pin "13") (pinfunction "PA0(ADC0/AREF/PCINT0)_13") (pintype "bidirectional"))
    )
    (net (code "73") (name "unconnected-(U2-PB0(PCINT8{slash}XTAL1{slash}CLKI)-Pad2)") (class "Default")
      (node (ref "U2") (pin "2") (pinfunction "PB0(PCINT8/XTAL1/CLKI)_2") (pintype "bidirectional"))
    )
    (net (code "74") (name "unconnected-(U2-PB1(PCINT9{slash}XTAL2)-Pad3)") (class "Default")
      (node (ref "U2") (pin "3") (pinfunction "PB1(PCINT9/XTAL2)_3") (pintype "bidirectional"))
    )
    (net (code "75") (name "unconnected-(U2-PB2(PCINT10{slash}INT0{slash}OC0A{slash}CKOUT)-Pad5)") (class "Default")
      (node (ref "U2") (pin "5") (pinfunction "PB2(PCINT10/INT0/OC0A/CKOUT)_5") (pintype "bidirectional"))
    )
    (net (code "76") (name "unconnected-(U5-RXTX-Pad3)") (class "Default")
      (node (ref "U5") (pin "3") (pinfunction "RXTX_3") (pintype "bidirectional"))
    )
    (net (code "77") (name "unconnected-(U7-GPIO{slash}MFP5-Pad32)") (class "Default")
      (node (ref "U7") (pin "32") (pinfunction "GPIO/MFP5_32") (pintype "bidirectional"))
    )
    (net (code "78") (name "unconnected-(U7-HPL-Pad25)") (class "Default")
      (node (ref "U7") (pin "25") (pinfunction "HPL_25") (pintype "bidirectional"))
    )
    (net (code "79") (name "unconnected-(U7-HPR-Pad27)") (class "Default")
      (node (ref "U7") (pin "27") (pinfunction "HPR_27") (pintype "bidirectional"))
    )
    (net (code "80") (name "unconnected-(U7-IN2_L-Pad15)") (class "Default")
      (node (ref "U7") (pin "15") (pinfunction "IN2_L_15") (pintype "bidirectional"))
    )
    (net (code "81") (name "unconnected-(U7-IN2_R-Pad16)") (class "Default")
      (node (ref "U7") (pin "16") (pinfunction "IN2_R_16") (pintype "bidirectional"))
    )
    (net (code "82") (name "unconnected-(U7-IN3_L-Pad20)") (class "Default")
      (node (ref "U7") (pin "20") (pinfunction "IN3_L_20") (pintype "bidirectional"))
    )
    (net (code "83") (name "unconnected-(U7-IN3_R-Pad21)") (class "Default")
      (node (ref "U7") (pin "21") (pinfunction "IN3_R_21") (pintype "bidirectional"))
    )
    (net (code "84") (name "unconnected-(U7-MICBIAS-Pad19)") (class "Default")
      (node (ref "U7") (pin "19") (pinfunction "MICBIAS_19") (pintype "bidirectional"))
    )
    (net (code "85") (name "unconnected-(USB-ID-Pad4)") (class "Default")
      (node (ref "USB") (pin "4") (pinfunction "ID_4") (pintype "bidirectional"))
    )
  )
)
